# AstroEQ_DIY_Etch.net
KiCad netlist of a schematic drawn in EAGLE
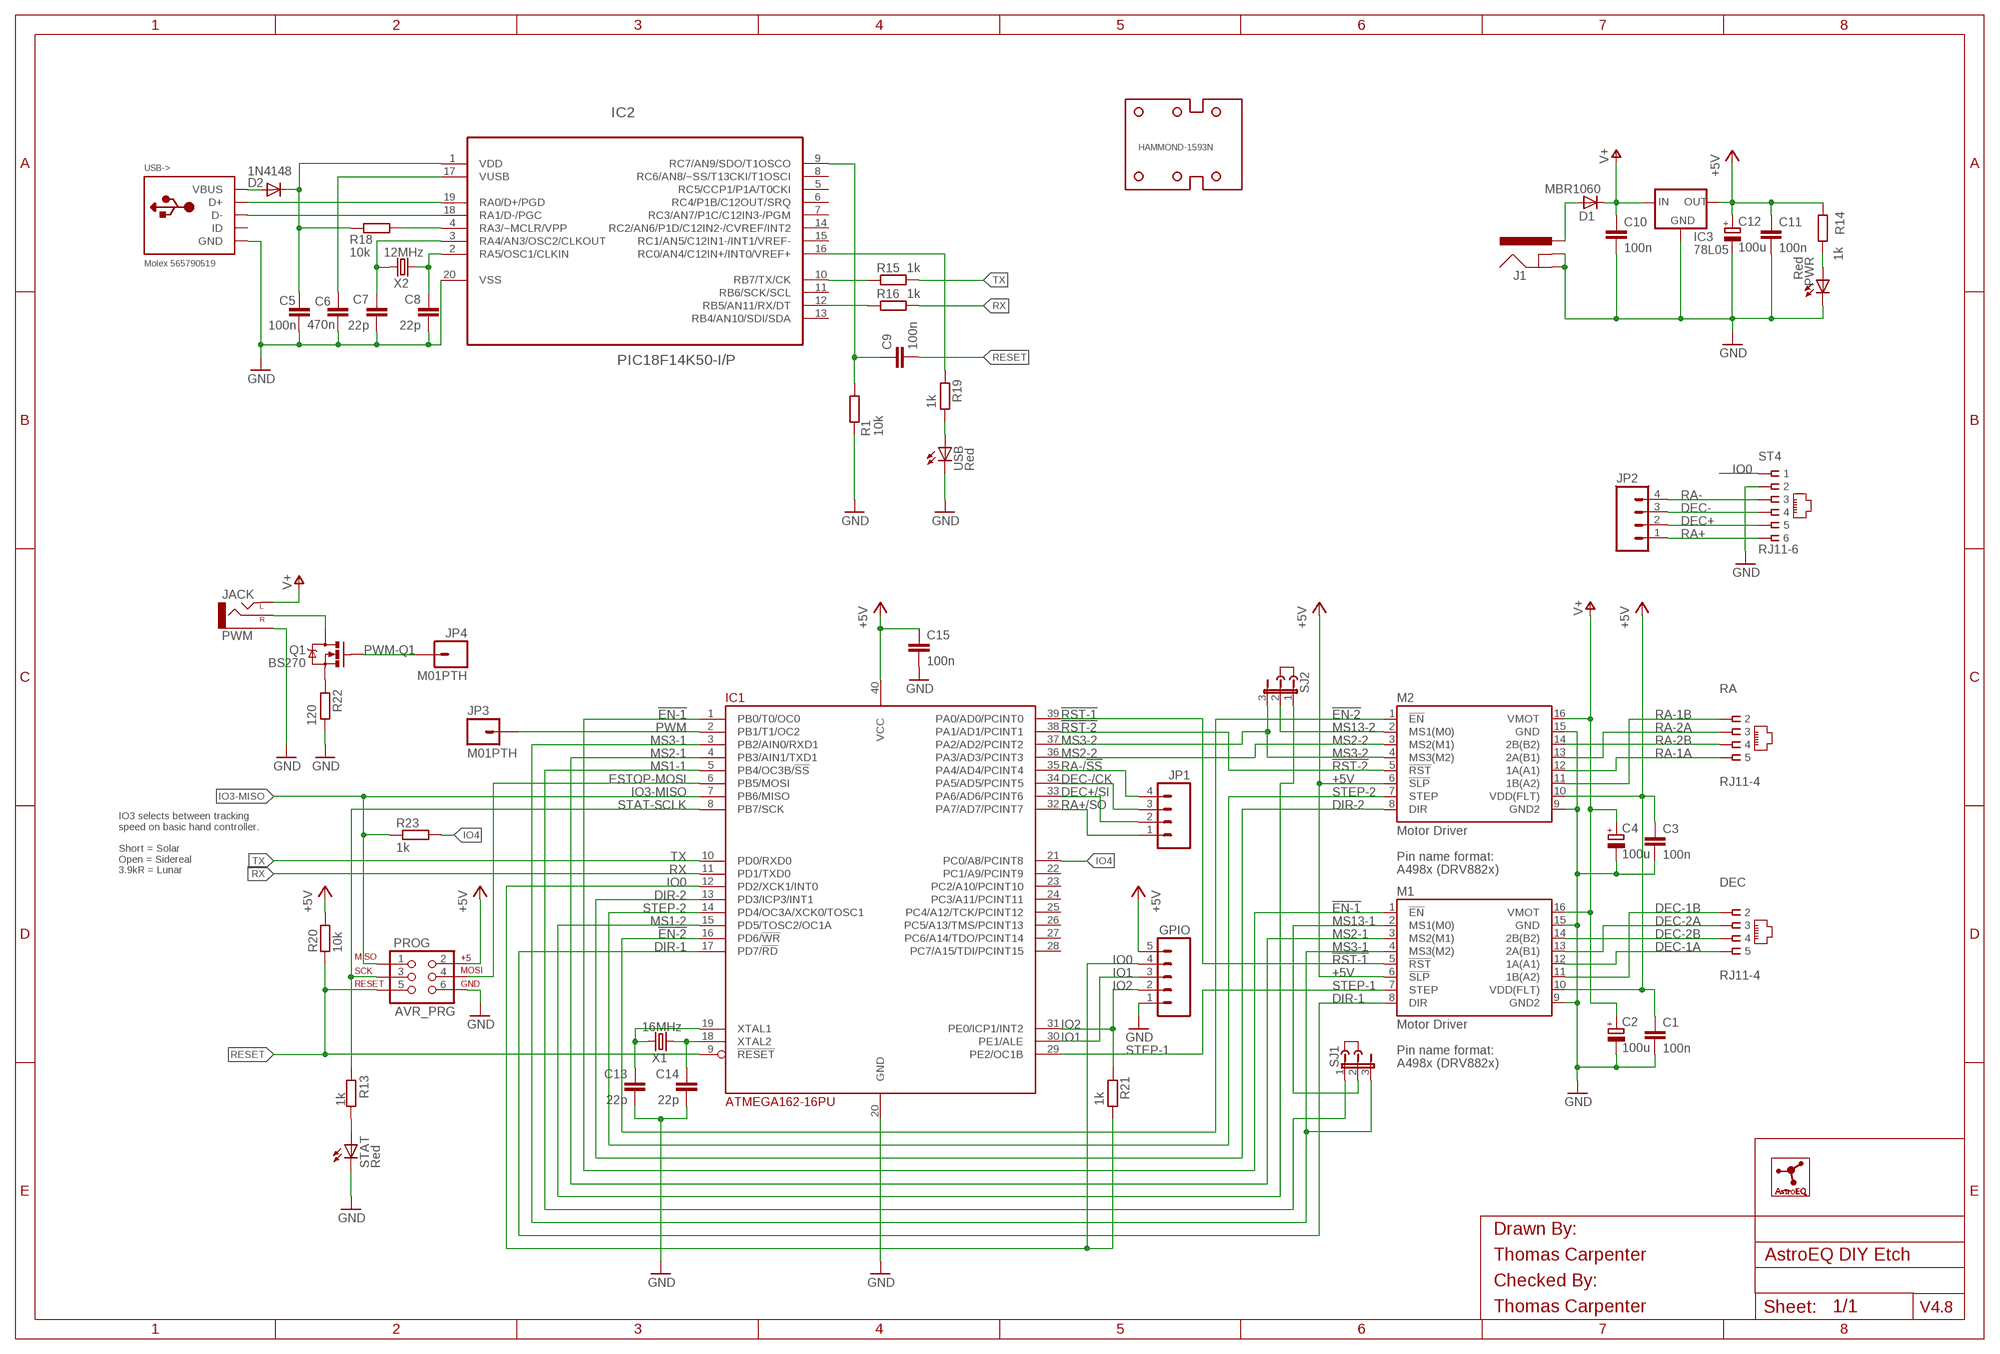
[diagram p0: schematic, sheet 1]

(export (version "E")
  (design (tool "Eeschema 10.0.6"))
  (components
    (comp (ref "C1")
      (value "100n")
      (footprint "eagle-import:C025-024X044")
      (fields (field (name "MF") "AVX") (field (name "MPN") "SR205C104KAR"))
      (libsource (lib "eagle-import") (part "C-EU025-024X044"))
    )
    (comp (ref "C2")
      (value "100u")
      (footprint "eagle-import:E2,5-7")
      (fields (field (name "MF") "MULTICOMP") (field (name "MPN") "MCGPR25V107M6.3X11"))
      (libsource (lib "eagle-import") (part "CPOL-EUE2.5-7"))
    )
    (comp (ref "C3")
      (value "100n")
      (footprint "eagle-import:C025-024X044")
      (fields (field (name "MF") "AVX") (field (name "MPN") "SR205C104KAR"))
      (libsource (lib "eagle-import") (part "C-EU025-024X044"))
    )
    (comp (ref "C4")
      (value "100u")
      (footprint "eagle-import:E2,5-7")
      (fields (field (name "MF") "MULTICOMP") (field (name "MPN") "MCGPR25V107M6.3X11"))
      (libsource (lib "eagle-import") (part "CPOL-EUE2.5-7"))
    )
    (comp (ref "C5")
      (value "100n")
      (footprint "eagle-import:C025-024X044")
      (fields (field (name "MF") "AVX") (field (name "MPN") "SR205C104KAR"))
      (libsource (lib "eagle-import") (part "C-EU025-024X044"))
    )
    (comp (ref "C6")
      (value "470n")
      (footprint "eagle-import:C025-024X044")
      (fields (field (name "MF") "KEMET") (field (name "MPN") "C320C474M5U5TA"))
      (libsource (lib "eagle-import") (part "C-EU025-024X044"))
    )
    (comp (ref "C7")
      (value "22p")
      (footprint "eagle-import:C025-024X044")
      (fields (field (name "MF") "AVX") (field (name "MPN") "SR151A220JAR"))
      (libsource (lib "eagle-import") (part "C-EU025-024X044"))
    )
    (comp (ref "C8")
      (value "22p")
      (footprint "eagle-import:C025-024X044")
      (fields (field (name "MF") "AVX") (field (name "MPN") "SR151A220JAR"))
      (libsource (lib "eagle-import") (part "C-EU025-024X044"))
    )
    (comp (ref "C9")
      (value "100n")
      (footprint "eagle-import:C025-024X044")
      (fields (field (name "MF") "AVX") (field (name "MPN") "SR205C104KAR"))
      (libsource (lib "eagle-import") (part "C-EU025-024X044"))
    )
    (comp (ref "C10")
      (value "100n")
      (footprint "eagle-import:C025-024X044")
      (fields (field (name "MF") "AVX") (field (name "MPN") "SR205C104KAR"))
      (libsource (lib "eagle-import") (part "C-EU025-024X044"))
    )
    (comp (ref "C11")
      (value "100n")
      (footprint "eagle-import:C025-024X044")
      (fields (field (name "MF") "AVX") (field (name "MPN") "SR205C104KAR"))
      (libsource (lib "eagle-import") (part "C-EU025-024X044"))
    )
    (comp (ref "C12")
      (value "100u")
      (footprint "eagle-import:E2,5-7")
      (fields (field (name "MF") "MULTICOMP") (field (name "MPN") "MCGPR25V107M6.3X11"))
      (libsource (lib "eagle-import") (part "CPOL-EUE2.5-7"))
    )
    (comp (ref "C13")
      (value "22p")
      (footprint "eagle-import:C025-024X044")
      (fields (field (name "MF") "AVX") (field (name "MPN") "SR151A220JAR"))
      (libsource (lib "eagle-import") (part "C-EU025-024X044"))
    )
    (comp (ref "C14")
      (value "22p")
      (footprint "eagle-import:C025-024X044")
      (fields (field (name "MF") "AVX") (field (name "MPN") "SR151A220JAR"))
      (libsource (lib "eagle-import") (part "C-EU025-024X044"))
    )
    (comp (ref "C15")
      (value "100n")
      (footprint "eagle-import:C025-024X044")
      (fields (field (name "MF") "AVX") (field (name "MPN") "SR205C104KAR"))
      (libsource (lib "eagle-import") (part "C-EU025-024X044"))
    )
    (comp (ref "D1")
      (value "MBR1060")
      (footprint "eagle-import:C221B1A")
      (fields (field (name "MF") "MULTICOMP"))
      (libsource (lib "eagle-import") (part "MUR820"))
    )
    (comp (ref "D2")
      (value "1N4148")
      (footprint "eagle-import:DIODE-1N4148")
      (fields (field (name "MF") "MULTICOMP") (field (name "MPN") "1N4148."))
      (libsource (lib "eagle-import") (part "DIODE1N4148"))
    )
    (comp (ref "DEC")
      (value "RJ11-4")
      (footprint "eagle-import:RJ11-NO_SHIELD-4")
      (fields (field (name "MF") "MOLEX") (field (name "MPN") "95501-2641"))
      (libsource (lib "eagle-import") (part "RJ11-4"))
    )
    (comp (ref "GPIO")
      (value "M05PTH")
      (footprint "eagle-import:1X05")
      (fields (field (name "MF") "CYNERGY3") (field (name "MPN") "SSF211X050"))
      (libsource (lib "eagle-import") (part "M05PTH"))
    )
    (comp (ref "HAMMOND-1593N")
      (value "HAMMOND-1593N-4HOLE")
      (footprint "eagle-import:HAMMOND-1593N4HOLES")
      (fields (field (name "MF") "HAMMOND") (field (name "MPN") "1593NBK"))
      (libsource (lib "eagle-import") (part "HAMMOND-1593N-4HOLE"))
    )
    (comp (ref "IC1")
      (value "ATMEGA162-16PU")
      (footprint "eagle-import:DIL40")
      (fields (field (name "MF") "ATMEL"))
      (libsource (lib "eagle-import") (part "ATMEGA162-16PU"))
    )
    (comp (ref "IC2")
      (value "PIC18F14K50-I/P")
      (footprint "eagle-import:DIL20")
      (fields (field (name "MF") "MICROCHIP"))
      (libsource (lib "eagle-import") (part "PIC18F14K50-I/P"))
    )
    (comp (ref "IC3")
      (value "78L05")
      (footprint "eagle-import:TO-92")
      (fields (field (name "MF") "FAIRCHILD SEMICONDUCTOR") (field (name "MPN") "LM78L05ACZX"))
      (libsource (lib "eagle-import") (part "V_REG_78XXTO-92"))
    )
    (comp (ref "J1")
      (value "POWER_JACKPTH")
      (footprint "eagle-import:POWER_JACK_PTH")
      (fields (field (name "MF") "MULTICOMP") (field (name "MPN") "MJ-179PH"))
      (libsource (lib "eagle-import") (part "POWER_JACKPTH"))
    )
    (comp (ref "J2")
      (value "JUMPER")
      (footprint "eagle-import:JUMP")
      (libsource (lib "eagle-import") (part "JUMPER"))
    )
    (comp (ref "J3")
      (value "JUMPER")
      (footprint "eagle-import:JUMP")
      (libsource (lib "eagle-import") (part "JUMPER"))
    )
    (comp (ref "JP1")
      (value "M04PTH")
      (footprint "eagle-import:1X04")
      (libsource (lib "eagle-import") (part "M04PTH"))
    )
    (comp (ref "JP2")
      (value "M04PTH")
      (footprint "eagle-import:1X04")
      (libsource (lib "eagle-import") (part "M04PTH"))
    )
    (comp (ref "JP3")
      (value "M01PTH")
      (footprint "eagle-import:1X01")
      (libsource (lib "eagle-import") (part "M01PTH"))
    )
    (comp (ref "JP4")
      (value "M01PTH")
      (footprint "eagle-import:1X01")
      (libsource (lib "eagle-import") (part "M01PTH"))
    )
    (comp (ref "LOGO1")
      (value "ASTROEQ5MM")
      (footprint "eagle-import:ASTROEQ-SMALL")
      (libsource (lib "eagle-import") (part "ASTROEQ5MM"))
    )
    (comp (ref "M1")
      (value "Motor Driver")
      (footprint "eagle-import:DIP16-W")
      (fields (field (name "MF") "SAMTEC") (field (name "MPN") "CES-116-01-T-S"))
      (libsource (lib "eagle-import") (part "A4983CARRIER"))
    )
    (comp (ref "M2")
      (value "Motor Driver")
      (footprint "eagle-import:DIP16-W")
      (fields (field (name "MF") "SAMTEC") (field (name "MPN") "CES-116-01-T-S"))
      (libsource (lib "eagle-import") (part "A4983CARRIER"))
    )
    (comp (ref "PROG")
      (value "AVR_PRG")
      (footprint "eagle-import:2X3")
      (fields (field (name "MF") "TE CONNECTIVITY / AMP") (field (name "MPN") "826632-3"))
      (libsource (lib "eagle-import") (part "AVR_SPI_PRG_6PTH"))
    )
    (comp (ref "PWM")
      (value "JACK")
      (footprint "eagle-import:AUDIO-JACK")
      (fields (field (name "MF") "CLIFF ELECTRONIC COMPONENTS") (field (name "MPN") "FC68131"))
      (libsource (lib "eagle-import") (part "AUDIO-JACKPTH"))
    )
    (comp (ref "PWR")
      (value "Red")
      (footprint "eagle-import:LED3MM")
      (fields (field (name "MF") "KINGBRIGHT") (field (name "MPN") "L-424HDT"))
      (libsource (lib "eagle-import") (part "LED3MM"))
    )
    (comp (ref "Q1")
      (value "BS270")
      (footprint "eagle-import:TO-92")
      (fields (field (name "MF") "FAIRCHILD SEMICONDUCTOR"))
      (libsource (lib "eagle-import") (part "MOSFET-NCHANNELPTH"))
    )
    (comp (ref "R1")
      (value "10k")
      (footprint "eagle-import:0204_7")
      (fields (field (name "MF") "MULTICOMP") (field (name "MPN") "MF12 10K"))
      (libsource (lib "eagle-import") (part "R-EU_0204/7"))
    )
    (comp (ref "R13")
      (value "1k")
      (footprint "eagle-import:0204_7")
      (fields (field (name "MF") "MULTICOMP") (field (name "MPN") "MF12 1K"))
      (libsource (lib "eagle-import") (part "R-EU_0204/7"))
    )
    (comp (ref "R14")
      (value "1k")
      (footprint "eagle-import:0204_7")
      (fields (field (name "MF") "MULTICOMP") (field (name "MPN") "MF12 1K"))
      (libsource (lib "eagle-import") (part "R-EU_0204/7"))
    )
    (comp (ref "R15")
      (value "1k")
      (footprint "eagle-import:0204_7")
      (fields (field (name "MF") "MULTICOMP") (field (name "MPN") "MF12 1K"))
      (libsource (lib "eagle-import") (part "R-EU_0204/7"))
    )
    (comp (ref "R16")
      (value "1k")
      (footprint "eagle-import:0204_7")
      (fields (field (name "MF") "MULTICOMP") (field (name "MPN") "MF12 1K"))
      (libsource (lib "eagle-import") (part "R-EU_0204/7"))
    )
    (comp (ref "R18")
      (value "10k")
      (footprint "eagle-import:0204_7")
      (fields (field (name "MF") "MULTICOMP") (field (name "MPN") "MF12 10K"))
      (libsource (lib "eagle-import") (part "R-EU_0204/7"))
    )
    (comp (ref "R19")
      (value "1k")
      (footprint "eagle-import:0204_7")
      (fields (field (name "MF") "MULTICOMP") (field (name "MPN") "MF12 1K"))
      (libsource (lib "eagle-import") (part "R-EU_0204/7"))
    )
    (comp (ref "R20")
      (value "10k")
      (footprint "eagle-import:0204_7")
      (fields (field (name "MF") "MULTICOMP") (field (name "MPN") "MF12 10K"))
      (libsource (lib "eagle-import") (part "R-EU_0204/7"))
    )
    (comp (ref "R21")
      (value "1k")
      (footprint "eagle-import:0204_7")
      (fields (field (name "MF") "MULTICOMP") (field (name "MPN") "MF12 1K"))
      (libsource (lib "eagle-import") (part "R-EU_0204/7"))
    )
    (comp (ref "R22")
      (value "120")
      (footprint "eagle-import:0204_7")
      (fields (field (name "MF") "MULTICOMP") (field (name "MPN") "MF12 120R"))
      (libsource (lib "eagle-import") (part "R-EU_0204/7"))
    )
    (comp (ref "R23")
      (value "1k")
      (footprint "eagle-import:0207_10")
      (fields (field (name "MF") "MULTICOMP") (field (name "MPN") "MF12 1K"))
      (libsource (lib "eagle-import") (part "R-EU_0207/10"))
    )
    (comp (ref "RA")
      (value "RJ11-4")
      (footprint "eagle-import:RJ11-NO_SHIELD-4")
      (fields (field (name "MF") "MOLEX") (field (name "MPN") "95501-2641"))
      (libsource (lib "eagle-import") (part "RJ11-4"))
    )
    (comp (ref "SJ1")
      (value "JP2EL")
      (footprint "eagle-import:JP2L")
      (libsource (lib "eagle-import") (part "JP2EL"))
    )
    (comp (ref "SJ2")
      (value "JP2EL")
      (footprint "eagle-import:JP2L")
      (libsource (lib "eagle-import") (part "JP2EL"))
    )
    (comp (ref "ST4")
      (value "RJ11-6")
      (footprint "eagle-import:RJ11-NO_SHIELD")
      (fields
        (field (name "MF") "TYCO ELECTRONICS")
        (field (name "MPN") "RJ11-2L-B")
        (field (name "MF_1") "MOLEX")
        (field (name "MPN_1") "95501-2661")
        (field (name "OC_FARNELL") "1536490")
      )
      (libsource (lib "eagle-import") (part "RJ11-2L-B"))
    )
    (comp (ref "STAT")
      (value "Red")
      (footprint "eagle-import:LED3MM")
      (fields (field (name "MF") "KINGBRIGHT") (field (name "MPN") "L-424HDT"))
      (libsource (lib "eagle-import") (part "LED3MM"))
    )
    (comp (ref "USB")
      (value "Red")
      (footprint "eagle-import:LED3MM")
      (fields (field (name "MF") "KINGBRIGHT") (field (name "MPN") "L-424HDT"))
      (libsource (lib "eagle-import") (part "LED3MM"))
    )
    (comp (ref "USB->")
      (value "Molex 565790519")
      (footprint "eagle-import:USB-MINIB-THM-MOLEX")
      (fields (field (name "MF") "MOLEX") (field (name "MPN") "565790519"))
      (libsource (lib "eagle-import") (part "USBMOLEX"))
    )
    (comp (ref "X1")
      (value "16MHz")
      (footprint "eagle-import:HC49US")
      (fields (field (name "MF") "TXC") (field (name "MPN") "9B-16.000MEEJ-B"))
      (libsource (lib "eagle-import") (part "CRYSTALHC49US"))
    )
    (comp (ref "X2")
      (value "12MHz")
      (footprint "eagle-import:HC49US")
      (fields (field (name "MF") "TXC") (field (name "MPN") "9B-12.000MAAJ-B"))
      (libsource (lib "eagle-import") (part "CRYSTALHC49US"))
    )
  )
  (nets
    (net (code "1") (name "+5V") (class "Default")
      (node (ref "C1") (pin "1") (pinfunction "1_1") (pintype "passive"))
      (node (ref "C11") (pin "1") (pinfunction "1_1") (pintype "passive"))
      (node (ref "C12") (pin "+") (pinfunction "+_+") (pintype "passive"))
      (node (ref "C15") (pin "1") (pinfunction "1_1") (pintype "passive"))
      (node (ref "C3") (pin "1") (pinfunction "1_1") (pintype "passive"))
      (node (ref "GPIO") (pin "5") (pinfunction "5_5") (pintype "passive"))
      (node (ref "IC1") (pin "40") (pinfunction "VCC_40") (pintype "power_in"))
      (node (ref "IC3") (pin "1") (pinfunction "OUT_1") (pintype "power_in"))
      (node (ref "M1") (pin "10") (pinfunction "VDD(FLT)_10") (pintype "power_in"))
      (node (ref "M1") (pin "6") (pinfunction "~{SLP}_6") (pintype "input"))
      (node (ref "M2") (pin "10") (pinfunction "VDD(FLT)_10") (pintype "power_in"))
      (node (ref "M2") (pin "6") (pinfunction "~{SLP}_6") (pintype "input"))
      (node (ref "PROG") (pin "2") (pinfunction "2_2") (pintype "passive"))
      (node (ref "R14") (pin "1") (pinfunction "1_1") (pintype "passive"))
      (node (ref "R20") (pin "2") (pinfunction "2_2") (pintype "passive"))
    )
    (net (code "2") (name "/DEC+") (class "Default")
      (node (ref "JP2") (pin "2") (pinfunction "2_2") (pintype "passive"))
      (node (ref "ST4") (pin "5") (pinfunction "5_5") (pintype "passive"))
    )
    (net (code "3") (name "/DEC+{slash}SI") (class "Default")
      (node (ref "IC1") (pin "33") (pinfunction "PA6/AD6/PCINT6_33") (pintype "bidirectional"))
      (node (ref "JP1") (pin "2") (pinfunction "2_2") (pintype "passive"))
    )
    (net (code "4") (name "/DEC-") (class "Default")
      (node (ref "JP2") (pin "3") (pinfunction "3_3") (pintype "passive"))
      (node (ref "ST4") (pin "4") (pinfunction "4_4") (pintype "passive"))
    )
    (net (code "5") (name "/DEC-1A") (class "Default")
      (node (ref "DEC") (pin "5") (pinfunction "5_5") (pintype "passive"))
      (node (ref "M1") (pin "12") (pinfunction "1A(A1)_12") (pintype "output"))
    )
    (net (code "6") (name "/DEC-1B") (class "Default")
      (node (ref "DEC") (pin "2") (pinfunction "2_2") (pintype "passive"))
      (node (ref "M1") (pin "11") (pinfunction "1B(A2)_11") (pintype "output"))
    )
    (net (code "7") (name "/DEC-2A") (class "Default")
      (node (ref "DEC") (pin "3") (pinfunction "3_3") (pintype "passive"))
      (node (ref "M1") (pin "13") (pinfunction "2A(B1)_13") (pintype "output"))
    )
    (net (code "8") (name "/DEC-2B") (class "Default")
      (node (ref "DEC") (pin "4") (pinfunction "4_4") (pintype "passive"))
      (node (ref "M1") (pin "14") (pinfunction "2B(B2)_14") (pintype "output"))
    )
    (net (code "9") (name "/DEC-{slash}CK") (class "Default")
      (node (ref "IC1") (pin "34") (pinfunction "PA5/AD5/PCINT5_34") (pintype "bidirectional"))
      (node (ref "JP1") (pin "3") (pinfunction "3_3") (pintype "passive"))
    )
    (net (code "10") (name "/DIR-1") (class "Default")
      (node (ref "IC1") (pin "17") (pinfunction "PD7/~{RD}_17") (pintype "bidirectional"))
      (node (ref "M1") (pin "8") (pinfunction "DIR_8") (pintype "input"))
    )
    (net (code "11") (name "/DIR-2") (class "Default")
      (node (ref "IC1") (pin "13") (pinfunction "PD3/ICP3/INT1_13") (pintype "bidirectional"))
      (node (ref "M2") (pin "8") (pinfunction "DIR_8") (pintype "input"))
    )
    (net (code "12") (name "/ESTOP-MOSI") (class "Default")
      (node (ref "IC1") (pin "6") (pinfunction "PB5/MOSI_6") (pintype "bidirectional"))
      (node (ref "PROG") (pin "4") (pinfunction "4_4") (pintype "passive"))
    )
    (net (code "13") (name "/IO0") (class "Default")
      (node (ref "GPIO") (pin "4") (pinfunction "4_4") (pintype "passive"))
      (node (ref "IC1") (pin "12") (pinfunction "PD2/XCK1/INT0_12") (pintype "bidirectional"))
      (node (ref "R21") (pin "1") (pinfunction "1_1") (pintype "passive"))
      (node (ref "ST4") (pin "1") (pinfunction "1_1") (pintype "passive"))
    )
    (net (code "14") (name "/IO1") (class "Default")
      (node (ref "GPIO") (pin "3") (pinfunction "3_3") (pintype "passive"))
      (node (ref "IC1") (pin "30") (pinfunction "PE1/ALE_30") (pintype "bidirectional"))
    )
    (net (code "15") (name "/IO2") (class "Default")
      (node (ref "GPIO") (pin "2") (pinfunction "2_2") (pintype "passive"))
      (node (ref "IC1") (pin "31") (pinfunction "PE0/ICP1/INT2_31") (pintype "bidirectional"))
      (node (ref "R21") (pin "2") (pinfunction "2_2") (pintype "passive"))
    )
    (net (code "16") (name "/MS1-1") (class "Default")
      (node (ref "IC1") (pin "5") (pinfunction "PB4/OC3B/~{SS}_5") (pintype "bidirectional"))
      (node (ref "SJ1") (pin "1") (pinfunction "1_1") (pintype "passive"))
    )
    (net (code "17") (name "/MS1-2") (class "Default")
      (node (ref "IC1") (pin "15") (pinfunction "PD5/TOSC2/OC1A_15") (pintype "bidirectional"))
      (node (ref "SJ2") (pin "1") (pinfunction "1_1") (pintype "passive"))
    )
    (net (code "18") (name "/MS2-1") (class "Default")
      (node (ref "IC1") (pin "4") (pinfunction "PB3/AIN1/TXD1_4") (pintype "bidirectional"))
      (node (ref "M1") (pin "3") (pinfunction "MS2(M1)_3") (pintype "input"))
    )
    (net (code "19") (name "/MS2-2") (class "Default")
      (node (ref "IC1") (pin "36") (pinfunction "PA3/AD3/PCINT3_36") (pintype "bidirectional"))
      (node (ref "M2") (pin "3") (pinfunction "MS2(M1)_3") (pintype "input"))
    )
    (net (code "20") (name "/MS3-1") (class "Default")
      (node (ref "IC1") (pin "3") (pinfunction "PB2/AIN0/RXD1_3") (pintype "bidirectional"))
      (node (ref "M1") (pin "4") (pinfunction "MS3(M2)_4") (pintype "input"))
      (node (ref "SJ1") (pin "3") (pinfunction "3_3") (pintype "passive"))
    )
    (net (code "21") (name "/MS3-2") (class "Default")
      (node (ref "IC1") (pin "37") (pinfunction "PA2/AD2/PCINT2_37") (pintype "bidirectional"))
      (node (ref "M2") (pin "4") (pinfunction "MS3(M2)_4") (pintype "input"))
      (node (ref "SJ2") (pin "3") (pinfunction "3_3") (pintype "passive"))
    )
    (net (code "22") (name "/MS13-1") (class "Default")
      (node (ref "M1") (pin "2") (pinfunction "MS1(M0)_2") (pintype "input"))
      (node (ref "SJ1") (pin "2") (pinfunction "2_2") (pintype "passive"))
    )
    (net (code "23") (name "/MS13-2") (class "Default")
      (node (ref "M2") (pin "2") (pinfunction "MS1(M0)_2") (pintype "input"))
      (node (ref "SJ2") (pin "2") (pinfunction "2_2") (pintype "passive"))
    )
    (net (code "24") (name "/PWM") (class "Default")
      (node (ref "IC1") (pin "2") (pinfunction "PB1/T1/OC2_2") (pintype "bidirectional"))
      (node (ref "JP3") (pin "1") (pinfunction "1_1") (pintype "passive"))
    )
    (net (code "25") (name "/PWM-Q1") (class "Default")
      (node (ref "JP4") (pin "1") (pinfunction "1_1") (pintype "passive"))
      (node (ref "Q1") (pin "2") (pinfunction "G_2") (pintype "passive"))
    )
    (net (code "26") (name "/RA+") (class "Default")
      (node (ref "JP2") (pin "1") (pinfunction "1_1") (pintype "passive"))
      (node (ref "ST4") (pin "6") (pinfunction "6_6") (pintype "passive"))
    )
    (net (code "27") (name "/RA+{slash}SO") (class "Default")
      (node (ref "IC1") (pin "32") (pinfunction "PA7/AD7/PCINT7_32") (pintype "bidirectional"))
      (node (ref "JP1") (pin "1") (pinfunction "1_1") (pintype "passive"))
    )
    (net (code "28") (name "/RA-") (class "Default")
      (node (ref "JP2") (pin "4") (pinfunction "4_4") (pintype "passive"))
      (node (ref "ST4") (pin "3") (pinfunction "3_3") (pintype "passive"))
    )
    (net (code "29") (name "/RA-1A") (class "Default")
      (node (ref "M2") (pin "12") (pinfunction "1A(A1)_12") (pintype "output"))
      (node (ref "RA") (pin "5") (pinfunction "5_5") (pintype "passive"))
    )
    (net (code "30") (name "/RA-1B") (class "Default")
      (node (ref "M2") (pin "11") (pinfunction "1B(A2)_11") (pintype "output"))
      (node (ref "RA") (pin "2") (pinfunction "2_2") (pintype "passive"))
    )
    (net (code "31") (name "/RA-2A") (class "Default")
      (node (ref "M2") (pin "13") (pinfunction "2A(B1)_13") (pintype "output"))
      (node (ref "RA") (pin "3") (pinfunction "3_3") (pintype "passive"))
    )
    (net (code "32") (name "/RA-2B") (class "Default")
      (node (ref "M2") (pin "14") (pinfunction "2B(B2)_14") (pintype "output"))
      (node (ref "RA") (pin "4") (pinfunction "4_4") (pintype "passive"))
    )
    (net (code "33") (name "/RA-{slash}~{SS}") (class "Default")
      (node (ref "IC1") (pin "35") (pinfunction "PA4/AD4/PCINT4_35") (pintype "bidirectional"))
      (node (ref "JP1") (pin "4") (pinfunction "4_4") (pintype "passive"))
    )
    (net (code "34") (name "/STAT-SCLK") (class "Default")
      (node (ref "IC1") (pin "8") (pinfunction "PB7/SCK_8") (pintype "bidirectional"))
      (node (ref "PROG") (pin "3") (pinfunction "3_3") (pintype "passive"))
      (node (ref "R13") (pin "1") (pinfunction "1_1") (pintype "passive"))
    )
    (net (code "35") (name "/STEP-1") (class "Default")
      (node (ref "IC1") (pin "29") (pinfunction "PE2/OC1B_29") (pintype "bidirectional"))
      (node (ref "M1") (pin "7") (pinfunction "STEP_7") (pintype "input"))
    )
    (net (code "36") (name "/STEP-2") (class "Default")
      (node (ref "IC1") (pin "14") (pinfunction "PD4/OC3A/XCK0/TOSC1_14") (pintype "bidirectional"))
      (node (ref "M2") (pin "7") (pinfunction "STEP_7") (pintype "input"))
    )
    (net (code "37") (name "/~{EN-1}") (class "Default")
      (node (ref "IC1") (pin "1") (pinfunction "PB0/T0/OC0_1") (pintype "bidirectional"))
      (node (ref "M1") (pin "1") (pinfunction "~{EN}_1") (pintype "input"))
    )
    (net (code "38") (name "/~{EN-2}") (class "Default")
      (node (ref "IC1") (pin "16") (pinfunction "PD6/~{WR}_16") (pintype "bidirectional"))
      (node (ref "M2") (pin "1") (pinfunction "~{EN}_1") (pintype "input"))
    )
    (net (code "39") (name "/~{RST-1}") (class "Default")
      (node (ref "IC1") (pin "39") (pinfunction "PA0/AD0/PCINT0_39") (pintype "bidirectional"))
      (node (ref "M1") (pin "5") (pinfunction "~{RST}_5") (pintype "input"))
    )
    (net (code "40") (name "/~{RST-2}") (class "Default")
      (node (ref "IC1") (pin "38") (pinfunction "PA1/AD1/PCINT1_38") (pintype "bidirectional"))
      (node (ref "M2") (pin "5") (pinfunction "~{RST}_5") (pintype "input"))
    )
    (net (code "41") (name "GND") (class "Default")
      (node (ref "C1") (pin "2") (pinfunction "2_2") (pintype "passive"))
      (node (ref "C10") (pin "2") (pinfunction "2_2") (pintype "passive"))
      (node (ref "C11") (pin "2") (pinfunction "2_2") (pintype "passive"))
      (node (ref "C12") (pin "-") (pinfunction "-_-") (pintype "passive"))
      (node (ref "C13") (pin "2") (pinfunction "2_2") (pintype "passive"))
      (node (ref "C14") (pin "2") (pinfunction "2_2") (pintype "passive"))
      (node (ref "C15") (pin "2") (pinfunction "2_2") (pintype "passive"))
      (node (ref "C2") (pin "-") (pinfunction "-_-") (pintype "passive"))
      (node (ref "C3") (pin "2") (pinfunction "2_2") (pintype "passive"))
      (node (ref "C4") (pin "-") (pinfunction "-_-") (pintype "passive"))
      (node (ref "C5") (pin "2") (pinfunction "2_2") (pintype "passive"))
      (node (ref "C6") (pin "1") (pinfunction "1_1") (pintype "passive"))
      (node (ref "C7") (pin "2") (pinfunction "2_2") (pintype "passive"))
      (node (ref "C8") (pin "2") (pinfunction "2_2") (pintype "passive"))
      (node (ref "GPIO") (pin "1") (pinfunction "1_1") (pintype "passive"))
      (node (ref "IC1") (pin "20") (pinfunction "GND_20") (pintype "power_in"))
      (node (ref "IC2") (pin "20") (pinfunction "VSS_20") (pintype "power_in"))
      (node (ref "IC3") (pin "2") (pinfunction "GND_2") (pintype "input"))
      (node (ref "J1") (pin "GND") (pinfunction "GND_GND") (pintype "bidirectional"))
      (node (ref "J1") (pin "GNDBREAK") (pinfunction "GNDBREAK_GNDBREAK") (pintype "bidirectional"))
      (node (ref "M1") (pin "15") (pinfunction "GND_15") (pintype "power_in"))
      (node (ref "M1") (pin "9") (pinfunction "GND2_9") (pintype "power_in"))
      (node (ref "M2") (pin "15") (pinfunction "GND_15") (pintype "power_in"))
      (node (ref "M2") (pin "9") (pinfunction "GND2_9") (pintype "power_in"))
      (node (ref "PROG") (pin "6") (pinfunction "6_6") (pintype "passive"))
      (node (ref "PWM") (pin "SLEEVE") (pinfunction "SLEEVE_SLEEVE") (pintype "bidirectional"))
      (node (ref "PWR") (pin "K") (pinfunction "C_K") (pintype "passive"))
      (node (ref "R1") (pin "2") (pinfunction "2_2") (pintype "passive"))
      (node (ref "R22") (pin "1") (pinfunction "1_1") (pintype "passive"))
      (node (ref "ST4") (pin "2") (pinfunction "2_2") (pintype "passive"))
      (node (ref "STAT") (pin "K") (pinfunction "C_K") (pintype "passive"))
      (node (ref "USB") (pin "K") (pinfunction "C_K") (pintype "passive"))
      (node (ref "USB->") (pin "GND") (pinfunction "GND_GND") (pintype "power_in"))
      (node (ref "USB->") (pin "GND1") (pinfunction "GND_GND1") (pintype "power_in"))
      (node (ref "USB->") (pin "GND4") (pinfunction "GND_GND4") (pintype "power_in"))
    )
    (net (code "42") (name "IO3-MISO") (class "Default")
      (node (ref "IC1") (pin "7") (pinfunction "PB6/MISO_7") (pintype "bidirectional"))
      (node (ref "PROG") (pin "1") (pinfunction "1_1") (pintype "passive"))
      (node (ref "R23") (pin "1") (pinfunction "1_1") (pintype "passive"))
    )
    (net (code "43") (name "IO4") (class "Default")
      (node (ref "IC1") (pin "21") (pinfunction "PC0/A8/PCINT8_21") (pintype "bidirectional"))
      (node (ref "R23") (pin "2") (pinfunction "2_2") (pintype "passive"))
    )
    (net (code "44") (name "Net-(D1-PadA)") (class "Default")
      (node (ref "D1") (pin "A") (pinfunction "A_A") (pintype "passive"))
      (node (ref "J1") (pin "PWR") (pinfunction "PWR_PWR") (pintype "bidirectional"))
    )
    (net (code "45") (name "Net-(D2-PadA)") (class "Default")
      (node (ref "D2") (pin "A") (pinfunction "A_A") (pintype "passive"))
      (node (ref "USB->") (pin "VBUS") (pinfunction "VBUS_VBUS") (pintype "power_in"))
    )
    (net (code "46") (name "Net-(IC1-XTAL1)") (class "Default")
      (node (ref "C13") (pin "1") (pinfunction "1_1") (pintype "passive"))
      (node (ref "IC1") (pin "19") (pinfunction "XTAL1_19") (pintype "input"))
      (node (ref "X1") (pin "2") (pinfunction "2_2") (pintype "passive"))
    )
    (net (code "47") (name "Net-(IC1-XTAL2)") (class "Default")
      (node (ref "C14") (pin "1") (pinfunction "1_1") (pintype "passive"))
      (node (ref "IC1") (pin "18") (pinfunction "XTAL2_18") (pintype "input"))
      (node (ref "X1") (pin "1") (pinfunction "1_1") (pintype "passive"))
    )
    (net (code "48") (name "Net-(IC2-RA0{slash}D+{slash}PGD)") (class "Default")
      (node (ref "IC2") (pin "19") (pinfunction "RA0/D+/PGD_19") (pintype "bidirectional"))
      (node (ref "USB->") (pin "D+") (pinfunction "D+_D+") (pintype "bidirectional"))
    )
    (net (code "49") (name "Net-(IC2-RA1{slash}D-{slash}PGC)") (class "Default")
      (node (ref "IC2") (pin "18") (pinfunction "RA1/D-/PGC_18") (pintype "bidirectional"))
      (node (ref "USB->") (pin "D-") (pinfunction "D-_D-") (pintype "bidirectional"))
    )
    (net (code "50") (name "Net-(IC2-RA3{slash}~{MCLR{slash}VPP})") (class "Default")
      (node (ref "IC2") (pin "4") (pinfunction "RA3/~{MCLR/VPP}_4") (pintype "input"))
      (node (ref "R18") (pin "1") (pinfunction "1_1") (pintype "passive"))
    )
    (net (code "51") (name "Net-(IC2-RA4{slash}AN3{slash}OSC2{slash}CLKOUT)") (class "Default")
      (node (ref "C7") (pin "1") (pinfunction "1_1") (pintype "passive"))
      (node (ref "IC2") (pin "3") (pinfunction "RA4/AN3/OSC2/CLKOUT_3") (pintype "bidirectional"))
      (node (ref "X2") (pin "2") (pinfunction "2_2") (pintype "passive"))
    )
    (net (code "52") (name "Net-(IC2-RA5{slash}OSC1{slash}CLKIN)") (class "Default")
      (node (ref "C8") (pin "1") (pinfunction "1_1") (pintype "passive"))
      (node (ref "IC2") (pin "2") (pinfunction "RA5/OSC1/CLKIN_2") (pintype "bidirectional"))
      (node (ref "X2") (pin "1") (pinfunction "1_1") (pintype "passive"))
    )
    (net (code "53") (name "Net-(IC2-RB5{slash}AN11{slash}RX{slash}DT)") (class "Default")
      (node (ref "IC2") (pin "12") (pinfunction "RB5/AN11/RX/DT_12") (pintype "bidirectional"))
      (node (ref "R16") (pin "2") (pinfunction "2_2") (pintype "passive"))
    )
    (net (code "54") (name "Net-(IC2-RB7{slash}TX{slash}CK)") (class "Default")
      (node (ref "IC2") (pin "10") (pinfunction "RB7/TX/CK_10") (pintype "bidirectional"))
      (node (ref "R15") (pin "2") (pinfunction "2_2") (pintype "passive"))
    )
    (net (code "55") (name "Net-(IC2-RC0{slash}AN4{slash}C12IN+{slash}INT0{slash}VREF+)") (class "Default")
      (node (ref "IC2") (pin "16") (pinfunction "RC0/AN4/C12IN+/INT0/VREF+_16") (pintype "bidirectional"))
      (node (ref "R19") (pin "2") (pinfunction "2_2") (pintype "passive"))
    )
    (net (code "56") (name "Net-(IC2-RC7{slash}AN9{slash}SDO{slash}T1OSCO)") (class "Default")
      (node (ref "C9") (pin "1") (pinfunction "1_1") (pintype "passive"))
      (node (ref "IC2") (pin "9") (pinfunction "RC7/AN9/SDO/T1OSCO_9") (pintype "bidirectional"))
      (node (ref "R1") (pin "1") (pinfunction "1_1") (pintype "passive"))
    )
    (net (code "57") (name "Net-(IC2-VDD)") (class "Default")
      (node (ref "C5") (pin "1") (pinfunction "1_1") (pintype "passive"))
      (node (ref "D2") (pin "C") (pinfunction "C_C") (pintype "passive"))
      (node (ref "IC2") (pin "1") (pinfunction "VDD_1") (pintype "power_in"))
      (node (ref "R18") (pin "2") (pinfunction "2_2") (pintype "passive"))
    )
    (net (code "58") (name "Net-(IC2-VUSB)") (class "Default")
      (node (ref "C6") (pin "2") (pinfunction "2_2") (pintype "passive"))
      (node (ref "IC2") (pin "17") (pinfunction "VUSB_17") (pintype "power_in"))
    )
    (net (code "59") (name "Net-(PWM-RIGHT)") (class "Default")
      (node (ref "PWM") (pin "RING") (pinfunction "RIGHT_RING") (pintype "bidirectional"))
      (node (ref "Q1") (pin "1") (pinfunction "D_1") (pintype "passive"))
    )
    (net (code "60") (name "Net-(PWR-PadA)") (class "Default")
      (node (ref "PWR") (pin "A") (pinfunction "A_A") (pintype "passive"))
      (node (ref "R14") (pin "2") (pinfunction "2_2") (pintype "passive"))
    )
    (net (code "61") (name "Net-(Q1-S)") (class "Default")
      (node (ref "Q1") (pin "3") (pinfunction "S_3") (pintype "passive"))
      (node (ref "R22") (pin "2") (pinfunction "2_2") (pintype "passive"))
    )
    (net (code "62") (name "Net-(R13-Pad2)") (class "Default")
      (node (ref "R13") (pin "2") (pinfunction "2_2") (pintype "passive"))
      (node (ref "STAT") (pin "A") (pinfunction "A_A") (pintype "passive"))
    )
    (net (code "63") (name "Net-(R19-Pad1)") (class "Default")
      (node (ref "R19") (pin "1") (pinfunction "1_1") (pintype "passive"))
      (node (ref "USB") (pin "A") (pinfunction "A_A") (pintype "passive"))
    )
    (net (code "64") (name "RESET") (class "Default")
      (node (ref "C9") (pin "2") (pinfunction "2_2") (pintype "passive"))
      (node (ref "IC1") (pin "9") (pinfunction "~{RESET}_9") (pintype "input"))
      (node (ref "PROG") (pin "5") (pinfunction "5_5") (pintype "passive"))
      (node (ref "R20") (pin "1") (pinfunction "1_1") (pintype "passive"))
    )
    (net (code "65") (name "RX") (class "Default")
      (node (ref "IC1") (pin "11") (pinfunction "PD1/TXD0_11") (pintype "bidirectional"))
      (node (ref "R16") (pin "1") (pinfunction "1_1") (pintype "passive"))
    )
    (net (code "66") (name "TX") (class "Default")
      (node (ref "IC1") (pin "10") (pinfunction "PD0/RXD0_10") (pintype "bidirectional"))
      (node (ref "R15") (pin "1") (pinfunction "1_1") (pintype "passive"))
    )
    (net (code "67") (name "V+") (class "Default")
      (node (ref "C10") (pin "1") (pinfunction "1_1") (pintype "passive"))
      (node (ref "C2") (pin "+") (pinfunction "+_+") (pintype "passive"))
      (node (ref "C4") (pin "+") (pinfunction "+_+") (pintype "passive"))
      (node (ref "D1") (pin "C") (pinfunction "C_C") (pintype "passive"))
      (node (ref "IC3") (pin "3") (pinfunction "IN_3") (pintype "input"))
      (node (ref "M1") (pin "16") (pinfunction "VMOT_16") (pintype "power_in"))
      (node (ref "M2") (pin "16") (pinfunction "VMOT_16") (pintype "power_in"))
      (node (ref "PWM") (pin "TIP") (pinfunction "LEFT_TIP") (pintype "bidirectional"))
    )
    (net (code "68") (name "unconnected-(IC1-PC1{slash}A9{slash}PCINT9-Pad22)") (class "Default")
      (node (ref "IC1") (pin "22") (pinfunction "PC1/A9/PCINT9_22") (pintype "bidirectional"))
    )
    (net (code "69") (name "unconnected-(IC1-PC2{slash}A10{slash}PCINT10-Pad23)") (class "Default")
      (node (ref "IC1") (pin "23") (pinfunction "PC2/A10/PCINT10_23") (pintype "bidirectional"))
    )
    (net (code "70") (name "unconnected-(IC1-PC3{slash}A11{slash}PCINT11-Pad24)") (class "Default")
      (node (ref "IC1") (pin "24") (pinfunction "PC3/A11/PCINT11_24") (pintype "bidirectional"))
    )
    (net (code "71") (name "unconnected-(IC1-PC4{slash}A12{slash}TCK{slash}PCINT12-Pad25)") (class "Default")
      (node (ref "IC1") (pin "25") (pinfunction "PC4/A12/TCK/PCINT12_25") (pintype "bidirectional"))
    )
    (net (code "72") (name "unconnected-(IC1-PC5{slash}A13{slash}TMS{slash}PCINT13-Pad26)") (class "Default")
      (node (ref "IC1") (pin "26") (pinfunction "PC5/A13/TMS/PCINT13_26") (pintype "bidirectional"))
    )
    (net (code "73") (name "unconnected-(IC1-PC6{slash}A14{slash}TDO{slash}PCINT14-Pad27)") (class "Default")
      (node (ref "IC1") (pin "27") (pinfunction "PC6/A14/TDO/PCINT14_27") (pintype "bidirectional"))
    )
    (net (code "74") (name "unconnected-(IC1-PC7{slash}A15{slash}TDI{slash}PCINT15-Pad28)") (class "Default")
      (node (ref "IC1") (pin "28") (pinfunction "PC7/A15/TDI/PCINT15_28") (pintype "bidirectional"))
    )
    (net (code "75") (name "unconnected-(IC2-RB4{slash}AN10{slash}SDI{slash}SDA-Pad13)") (class "Default")
      (node (ref "IC2") (pin "13") (pinfunction "RB4/AN10/SDI/SDA_13") (pintype "bidirectional"))
    )
    (net (code "76") (name "unconnected-(IC2-RB6{slash}SCK{slash}SCL-Pad11)") (class "Default")
      (node (ref "IC2") (pin "11") (pinfunction "RB6/SCK/SCL_11") (pintype "bidirectional"))
    )
    (net (code "77") (name "unconnected-(IC2-RC1{slash}AN5{slash}C12IN1-{slash}INT1{slash}VREF--Pad15)") (class "Default")
      (node (ref "IC2") (pin "15") (pinfunction "RC1/AN5/C12IN1-/INT1/VREF-_15") (pintype "bidirectional"))
    )
    (net (code "78") (name "unconnected-(IC2-RC2{slash}AN6{slash}P1D{slash}C12IN2-{slash}CVREF{slash}INT2-Pad14)") (class "Default")
      (node (ref "IC2") (pin "14") (pinfunction "RC2/AN6/P1D/C12IN2-/CVREF/INT2_14") (pintype "bidirectional"))
    )
    (net (code "79") (name "unconnected-(IC2-RC3{slash}AN7{slash}P1C{slash}C12IN3-{slash}PGM-Pad7)") (class "Default")
      (node (ref "IC2") (pin "7") (pinfunction "RC3/AN7/P1C/C12IN3-/PGM_7") (pintype "bidirectional"))
    )
    (net (code "80") (name "unconnected-(IC2-RC4{slash}P1B{slash}C12OUT{slash}SRQ-Pad6)") (class "Default")
      (node (ref "IC2") (pin "6") (pinfunction "RC4/P1B/C12OUT/SRQ_6") (pintype "bidirectional"))
    )
    (net (code "81") (name "unconnected-(IC2-RC5{slash}CCP1{slash}P1A{slash}T0CKI-Pad5)") (class "Default")
      (node (ref "IC2") (pin "5") (pinfunction "RC5/CCP1/P1A/T0CKI_5") (pintype "bidirectional"))
    )
    (net (code "82") (name "unconnected-(IC2-RC6{slash}AN8{slash}~{SS{slash}T13CKI{slash}T1OSCI}-Pad8)") (class "Default")
      (node (ref "IC2") (pin "8") (pinfunction "RC6/AN8/~{SS/T13CKI/T1OSCI}_8") (pintype "bidirectional"))
    )
    (net (code "83") (name "unconnected-(USB->-PadID)") (class "Default")
      (node (ref "USB->") (pin "ID") (pinfunction "ID_ID") (pintype "bidirectional"))
    )
  )
)
